# PinkReq.net
KiCad netlist of a schematic drawn in EAGLE
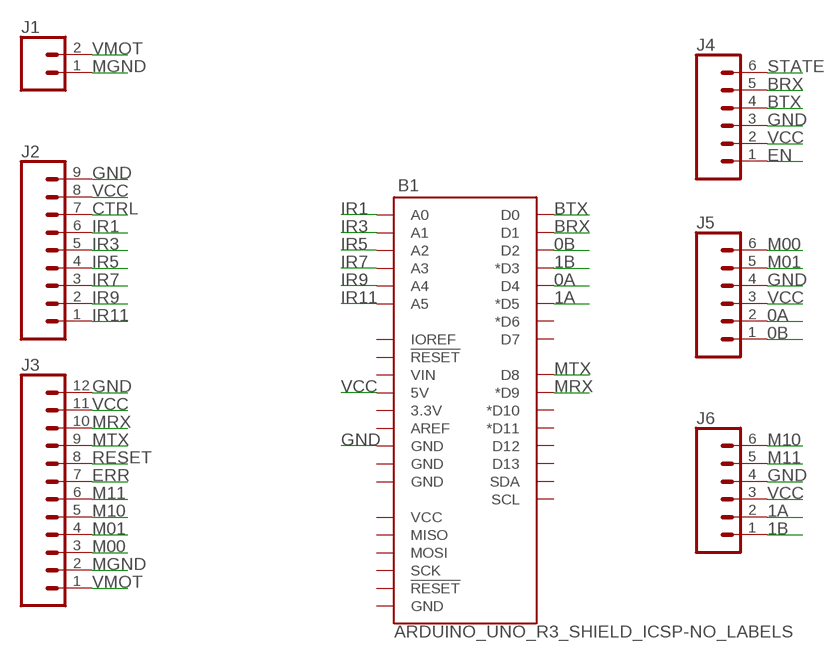
[diagram p0: schematic, sheet 1]

(export (version "E")
  (design (tool "Eeschema 10.0.6"))
  (components
    (comp (ref "B1")
      (value "ARDUINO_UNO_R3_SHIELD_ICSP-NO_LABELS")
      (footprint "eagle-import:UNO_R3_SHIELD_ICSP_NOLABELS")
      (libsource (lib "eagle-import") (part "ARDUINO_UNO_R3_SHIELD_ICSP-NO_LABELS"))
    )
    (comp (ref "J1")
      (value "CONN_025MM")
      (footprint "eagle-import:SCREWTERMINAL-5MM-2")
      (libsource (lib "eagle-import") (part "CONN_025MM"))
    )
    (comp (ref "J2")
      (value "CONN_09LOCK")
      (footprint "eagle-import:1X09_LOCK")
      (libsource (lib "eagle-import") (part "CONN_09LOCK"))
    )
    (comp (ref "J3")
      (value "CONN_12LOCK")
      (footprint "eagle-import:1X12_LOCK")
      (libsource (lib "eagle-import") (part "CONN_12LOCK"))
    )
    (comp (ref "J4")
      (value "CONN_06FEMALE_LOCK")
      (footprint "eagle-import:1X06_FEMALE_LOCK.010")
      (libsource (lib "eagle-import") (part "CONN_06FEMALE_LOCK"))
    )
    (comp (ref "J5")
      (value "CONN_06FEMALE_LOCK")
      (footprint "eagle-import:1X06_FEMALE_LOCK.010")
      (libsource (lib "eagle-import") (part "CONN_06FEMALE_LOCK"))
    )
    (comp (ref "J6")
      (value "CONN_06FEMALE_LOCK")
      (footprint "eagle-import:1X06_FEMALE_LOCK.010")
      (libsource (lib "eagle-import") (part "CONN_06FEMALE_LOCK"))
    )
  )
  (nets
    (net (code "1") (name "/0A") (class "Default")
      (node (ref "B1") (pin "D4") (pinfunction "D4_D4") (pintype "bidirectional"))
      (node (ref "J5") (pin "2") (pinfunction "2_2") (pintype "passive"))
    )
    (net (code "2") (name "/0B") (class "Default")
      (node (ref "B1") (pin "D2") (pinfunction "D2_D2") (pintype "bidirectional"))
      (node (ref "J5") (pin "1") (pinfunction "1_1") (pintype "passive"))
    )
    (net (code "3") (name "/1A") (class "Default")
      (node (ref "B1") (pin "D5") (pinfunction "*D5_D5") (pintype "bidirectional"))
      (node (ref "J6") (pin "2") (pinfunction "2_2") (pintype "passive"))
    )
    (net (code "4") (name "/1B") (class "Default")
      (node (ref "B1") (pin "D3") (pinfunction "*D3_D3") (pintype "bidirectional"))
      (node (ref "J6") (pin "1") (pinfunction "1_1") (pintype "passive"))
    )
    (net (code "5") (name "/BRX") (class "Default")
      (node (ref "B1") (pin "TX") (pinfunction "D1_TX") (pintype "bidirectional"))
      (node (ref "J4") (pin "5") (pinfunction "5_5") (pintype "passive"))
    )
    (net (code "6") (name "/BTX") (class "Default")
      (node (ref "B1") (pin "RX") (pinfunction "D0_RX") (pintype "bidirectional"))
      (node (ref "J4") (pin "4") (pinfunction "4_4") (pintype "passive"))
    )
    (net (code "7") (name "/CTRL") (class "Default")
      (node (ref "J2") (pin "7") (pinfunction "7_7") (pintype "passive"))
    )
    (net (code "8") (name "/EN") (class "Default")
      (node (ref "J4") (pin "1") (pinfunction "1_1") (pintype "passive"))
    )
    (net (code "9") (name "/ERR") (class "Default")
      (node (ref "J3") (pin "7") (pinfunction "7_7") (pintype "passive"))
    )
    (net (code "10") (name "/GND") (class "Default")
      (node (ref "B1") (pin "GND@2") (pinfunction "GND_GND@2") (pintype "bidirectional"))
      (node (ref "J2") (pin "9") (pinfunction "9_9") (pintype "passive"))
      (node (ref "J3") (pin "12") (pinfunction "12_12") (pintype "passive"))
      (node (ref "J4") (pin "3") (pinfunction "3_3") (pintype "passive"))
      (node (ref "J5") (pin "4") (pinfunction "4_4") (pintype "passive"))
      (node (ref "J6") (pin "4") (pinfunction "4_4") (pintype "passive"))
    )
    (net (code "11") (name "/IR1") (class "Default")
      (node (ref "B1") (pin "A0") (pinfunction "A0_A0") (pintype "bidirectional"))
      (node (ref "J2") (pin "6") (pinfunction "6_6") (pintype "passive"))
    )
    (net (code "12") (name "/IR3") (class "Default")
      (node (ref "B1") (pin "A1") (pinfunction "A1_A1") (pintype "bidirectional"))
      (node (ref "J2") (pin "5") (pinfunction "5_5") (pintype "passive"))
    )
    (net (code "13") (name "/IR5") (class "Default")
      (node (ref "B1") (pin "A2") (pinfunction "A2_A2") (pintype "bidirectional"))
      (node (ref "J2") (pin "4") (pinfunction "4_4") (pintype "passive"))
    )
    (net (code "14") (name "/IR7") (class "Default")
      (node (ref "B1") (pin "A3") (pinfunction "A3_A3") (pintype "bidirectional"))
      (node (ref "J2") (pin "3") (pinfunction "3_3") (pintype "passive"))
    )
    (net (code "15") (name "/IR9") (class "Default")
      (node (ref "B1") (pin "A4") (pinfunction "A4_A4") (pintype "bidirectional"))
      (node (ref "J2") (pin "2") (pinfunction "2_2") (pintype "passive"))
    )
    (net (code "16") (name "/IR11") (class "Default")
      (node (ref "B1") (pin "A5") (pinfunction "A5_A5") (pintype "bidirectional"))
      (node (ref "J2") (pin "1") (pinfunction "1_1") (pintype "passive"))
    )
    (net (code "17") (name "/M00") (class "Default")
      (node (ref "J3") (pin "3") (pinfunction "3_3") (pintype "passive"))
      (node (ref "J5") (pin "6") (pinfunction "6_6") (pintype "passive"))
    )
    (net (code "18") (name "/M01") (class "Default")
      (node (ref "J3") (pin "4") (pinfunction "4_4") (pintype "passive"))
      (node (ref "J5") (pin "5") (pinfunction "5_5") (pintype "passive"))
    )
    (net (code "19") (name "/M10") (class "Default")
      (node (ref "J3") (pin "5") (pinfunction "5_5") (pintype "passive"))
      (node (ref "J6") (pin "6") (pinfunction "6_6") (pintype "passive"))
    )
    (net (code "20") (name "/M11") (class "Default")
      (node (ref "J3") (pin "6") (pinfunction "6_6") (pintype "passive"))
      (node (ref "J6") (pin "5") (pinfunction "5_5") (pintype "passive"))
    )
    (net (code "21") (name "/MGND") (class "Default")
      (node (ref "J1") (pin "1") (pinfunction "1_1") (pintype "passive"))
      (node (ref "J3") (pin "2") (pinfunction "2_2") (pintype "passive"))
    )
    (net (code "22") (name "/MRX") (class "Default")
      (node (ref "B1") (pin "D9") (pinfunction "*D9_D9") (pintype "bidirectional"))
      (node (ref "J3") (pin "10") (pinfunction "10_10") (pintype "passive"))
    )
    (net (code "23") (name "/MTX") (class "Default")
      (node (ref "B1") (pin "D8") (pinfunction "D8_D8") (pintype "bidirectional"))
      (node (ref "J3") (pin "9") (pinfunction "9_9") (pintype "passive"))
    )
    (net (code "24") (name "/RESET") (class "Default")
      (node (ref "J3") (pin "8") (pinfunction "8_8") (pintype "passive"))
    )
    (net (code "25") (name "/STATE") (class "Default")
      (node (ref "J4") (pin "6") (pinfunction "6_6") (pintype "passive"))
    )
    (net (code "26") (name "/VCC") (class "Default")
      (node (ref "B1") (pin "5V") (pinfunction "5V_5V") (pintype "bidirectional"))
      (node (ref "J2") (pin "8") (pinfunction "8_8") (pintype "passive"))
      (node (ref "J3") (pin "11") (pinfunction "11_11") (pintype "passive"))
      (node (ref "J4") (pin "2") (pinfunction "2_2") (pintype "passive"))
      (node (ref "J5") (pin "3") (pinfunction "3_3") (pintype "passive"))
      (node (ref "J6") (pin "3") (pinfunction "3_3") (pintype "passive"))
    )
    (net (code "27") (name "/VMOT") (class "Default")
      (node (ref "J1") (pin "2") (pinfunction "2_2") (pintype "passive"))
      (node (ref "J3") (pin "1") (pinfunction "1_1") (pintype "passive"))
    )
    (net (code "28") (name "unconnected-(B1-*D6-PadD6)") (class "Default")
      (node (ref "B1") (pin "D6") (pinfunction "*D6_D6") (pintype "bidirectional"))
    )
    (net (code "29") (name "unconnected-(B1-*D10-PadD10)") (class "Default")
      (node (ref "B1") (pin "D10") (pinfunction "*D10_D10") (pintype "bidirectional"))
    )
    (net (code "30") (name "unconnected-(B1-*D11-PadD11)") (class "Default")
      (node (ref "B1") (pin "D11") (pinfunction "*D11_D11") (pintype "bidirectional"))
    )
    (net (code "31") (name "unconnected-(B1-GND-PadGND@0)") (class "Default")
      (node (ref "B1") (pin "GND@0") (pinfunction "GND_GND@0") (pintype "bidirectional"))
    )
    (net (code "32") (name "unconnected-(B1-GND-PadGND@1)") (class "Default")
      (node (ref "B1") (pin "GND@1") (pinfunction "GND_GND@1") (pintype "bidirectional"))
    )
    (net (code "33") (name "unconnected-(B1-GND-PadGND_ICSP)") (class "Default")
      (node (ref "B1") (pin "GND_ICSP") (pinfunction "GND_GND_ICSP") (pintype "bidirectional"))
    )
    (net (code "34") (name "unconnected-(B1-Pad3.3V)") (class "Default")
      (node (ref "B1") (pin "3.3V") (pinfunction "3.3V_3.3V") (pintype "bidirectional"))
    )
    (net (code "35") (name "unconnected-(B1-PadAREF)") (class "Default")
      (node (ref "B1") (pin "AREF") (pinfunction "AREF_AREF") (pintype "bidirectional"))
    )
    (net (code "36") (name "unconnected-(B1-PadD7)") (class "Default")
      (node (ref "B1") (pin "D7") (pinfunction "D7_D7") (pintype "bidirectional"))
    )
    (net (code "37") (name "unconnected-(B1-PadD12)") (class "Default")
      (node (ref "B1") (pin "D12") (pinfunction "D12_D12") (pintype "bidirectional"))
    )
    (net (code "38") (name "unconnected-(B1-PadD13)") (class "Default")
      (node (ref "B1") (pin "D13") (pinfunction "D13_D13") (pintype "bidirectional"))
    )
    (net (code "39") (name "unconnected-(B1-PadIOREF)") (class "Default")
      (node (ref "B1") (pin "IOREF") (pinfunction "IOREF_IOREF") (pintype "bidirectional"))
    )
    (net (code "40") (name "unconnected-(B1-PadMISO)") (class "Default")
      (node (ref "B1") (pin "MISO") (pinfunction "MISO_MISO") (pintype "bidirectional"))
    )
    (net (code "41") (name "unconnected-(B1-PadMOSI)") (class "Default")
      (node (ref "B1") (pin "MOSI") (pinfunction "MOSI_MOSI") (pintype "bidirectional"))
    )
    (net (code "42") (name "unconnected-(B1-PadSCK)") (class "Default")
      (node (ref "B1") (pin "SCK") (pinfunction "SCK_SCK") (pintype "bidirectional"))
    )
    (net (code "43") (name "unconnected-(B1-PadSCL)") (class "Default")
      (node (ref "B1") (pin "SCL") (pinfunction "SCL_SCL") (pintype "bidirectional"))
    )
    (net (code "44") (name "unconnected-(B1-PadSDA)") (class "Default")
      (node (ref "B1") (pin "SDA") (pinfunction "SDA_SDA") (pintype "bidirectional"))
    )
    (net (code "45") (name "unconnected-(B1-PadVIN)") (class "Default")
      (node (ref "B1") (pin "VIN") (pinfunction "VIN_VIN") (pintype "bidirectional"))
    )
    (net (code "46") (name "unconnected-(B1-VCC-Pad5V_ICSP)") (class "Default")
      (node (ref "B1") (pin "5V_ICSP") (pinfunction "VCC_5V_ICSP") (pintype "bidirectional"))
    )
    (net (code "47") (name "unconnected-(B1-~{RESET}-PadRES)") (class "Default")
      (node (ref "B1") (pin "RES") (pinfunction "~{RESET}_RES") (pintype "bidirectional"))
    )
    (net (code "48") (name "unconnected-(B1-~{RESET}-PadRST_ICSP)") (class "Default")
      (node (ref "B1") (pin "RST_ICSP") (pinfunction "~{RESET}_RST_ICSP") (pintype "bidirectional"))
    )
  )
)
